# control.net
KiCad netlist of a schematic drawn in Altium Designer
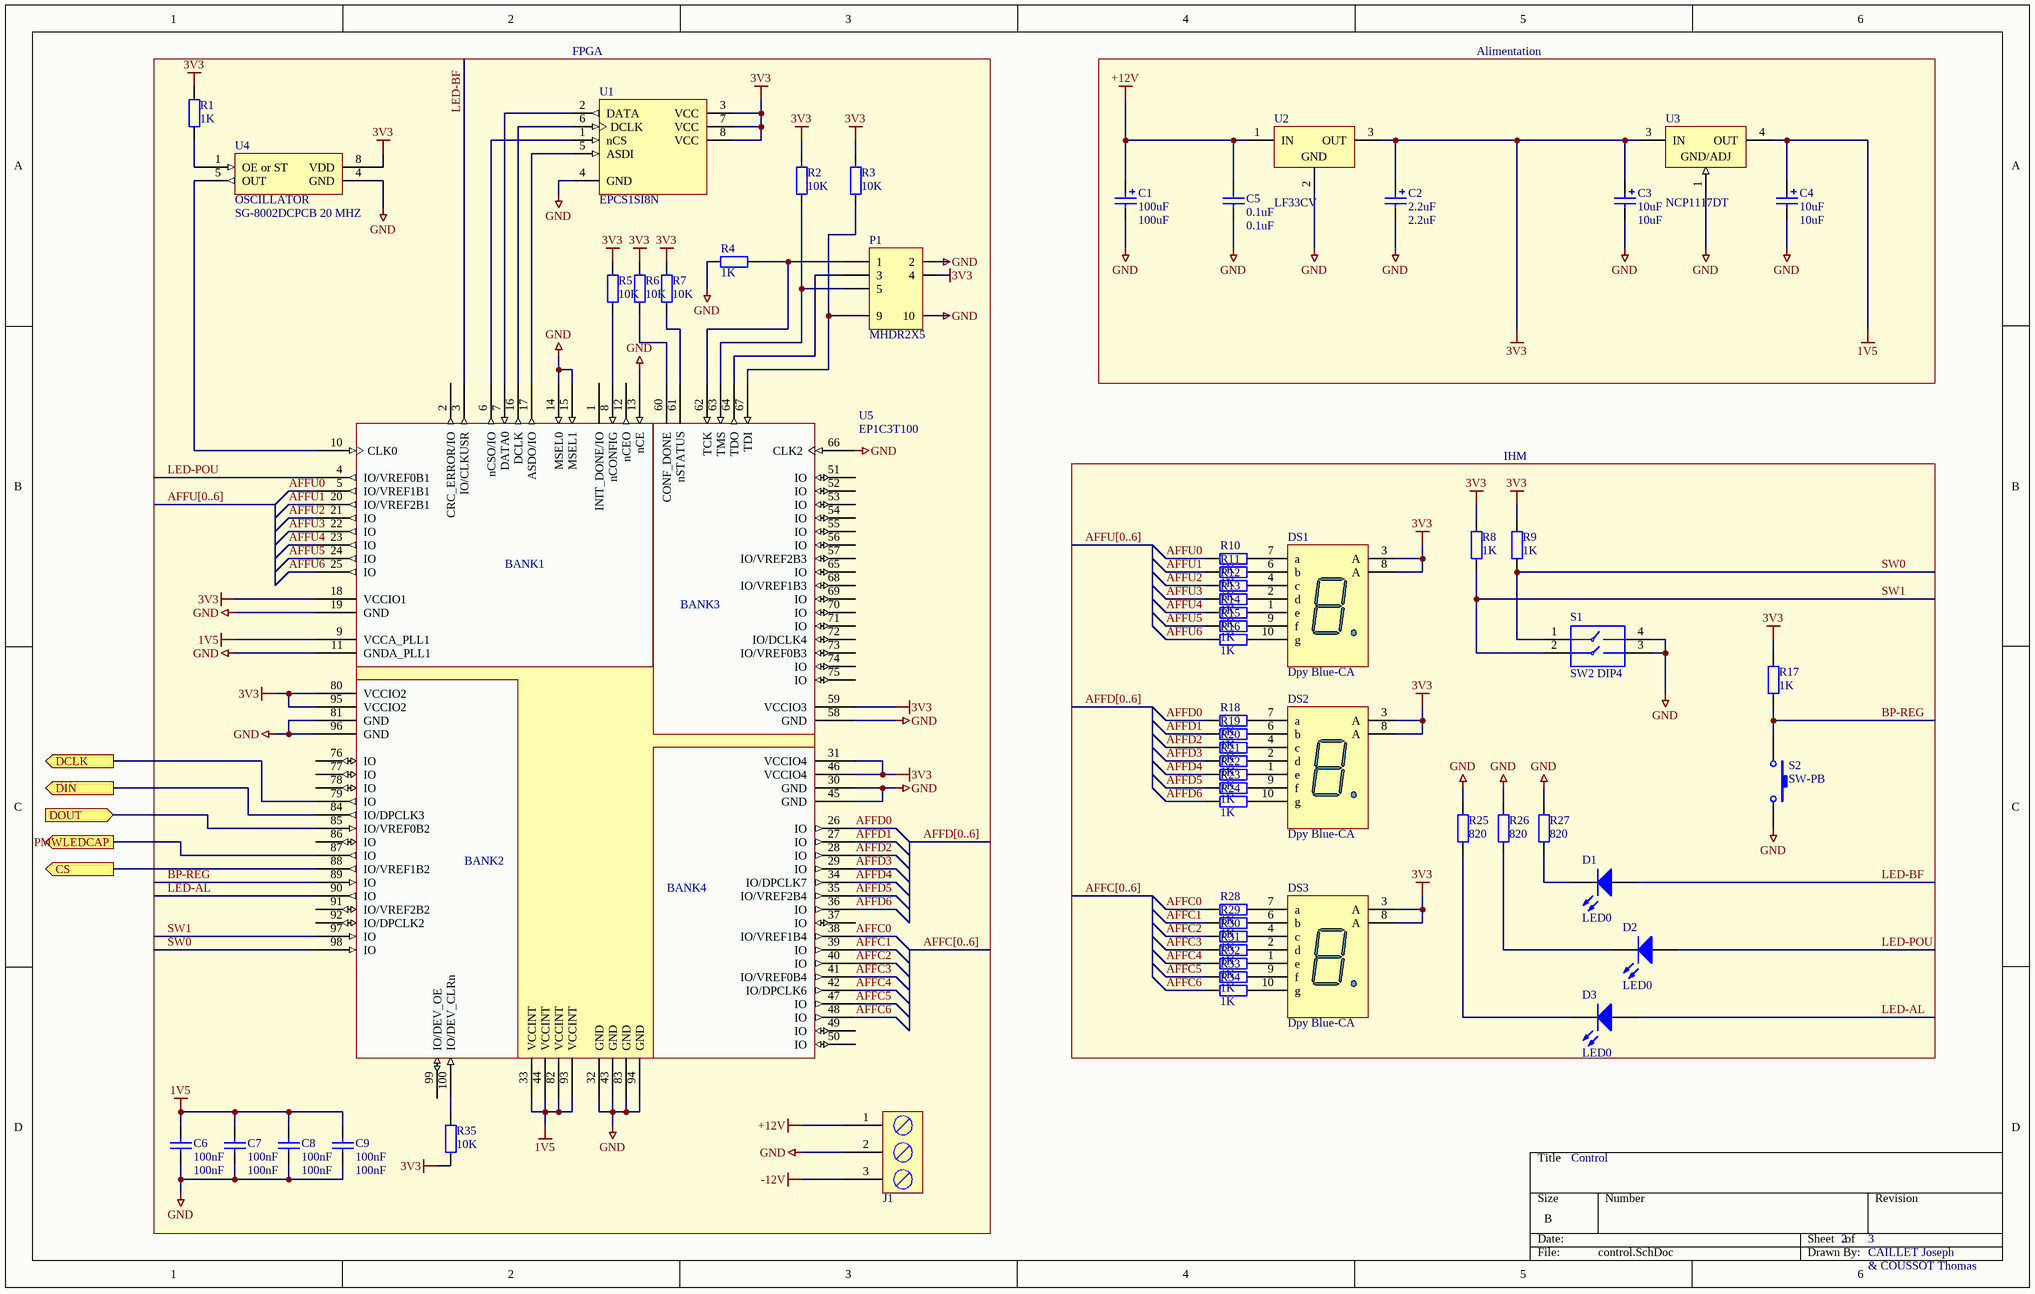
[diagram p0: control.SchDoc]

(export (version "E")
  (design (tool "Eeschema 10.0.6"))
  (components
    (comp (ref "C1")
      (value "100uF")
      (footprint "RB0.14/0.35")
      (description "Electrolytic Polarized Capacitor (Axial)")
      (fields (field (name "ALTIUM_VALUE") "100uF") (field (name "PUBLISHER") "Altium Limited"))
      (libsource (lib "Miscellaneous Devices") (part "Cap Pol2"))
    )
    (comp (ref "C2")
      (value "2.2uF")
      (footprint "RB0.1/0.2")
      (description "Electrolytic Polarized Capacitor (Axial)")
      (fields (field (name "ALTIUM_VALUE") "2.2uF") (field (name "PUBLISHER") "Altium Limited"))
      (libsource (lib "Miscellaneous Devices") (part "Cap Pol2"))
    )
    (comp (ref "C3")
      (value "10uF")
      (footprint "RB0.1/0.2")
      (description "Electrolytic Polarized Capacitor (Axial)")
      (fields (field (name "ALTIUM_VALUE") "10uF") (field (name "PUBLISHER") "Altium Limited"))
      (libsource (lib "Miscellaneous Devices") (part "Cap Pol2"))
    )
    (comp (ref "C4")
      (value "10uF")
      (footprint "RB0.1/0.2")
      (description "Electrolytic Polarized Capacitor (Axial)")
      (fields (field (name "ALTIUM_VALUE") "10uF") (field (name "PUBLISHER") "Altium Limited"))
      (libsource (lib "Miscellaneous Devices") (part "Cap Pol2"))
    )
    (comp (ref "C5")
      (value "0.1uF")
      (footprint "RAD-0.2")
      (description "Ceramic Multilayer Capacitor")
      (fields (field (name "ALTIUM_VALUE") "0.1uF") (field (name "PUBLISHER") "Altium Limited"))
      (libsource (lib "Miscellaneous Devices") (part "Cap"))
    )
    (comp (ref "C6")
      (value "100nF")
      (footprint "RAD-0.2")
      (description "Ceramic Multilayer Capacitor")
      (fields (field (name "ALTIUM_VALUE") "100nF") (field (name "PUBLISHER") "Altium Limited"))
      (libsource (lib "Miscellaneous Devices") (part "Cap"))
    )
    (comp (ref "C7")
      (value "100nF")
      (footprint "RAD-0.2")
      (description "Ceramic Multilayer Capacitor")
      (fields (field (name "ALTIUM_VALUE") "100nF") (field (name "PUBLISHER") "Altium Limited"))
      (libsource (lib "Miscellaneous Devices") (part "Cap"))
    )
    (comp (ref "C8")
      (value "100nF")
      (footprint "RAD-0.2")
      (description "Ceramic Multilayer Capacitor")
      (fields (field (name "ALTIUM_VALUE") "100nF") (field (name "PUBLISHER") "Altium Limited"))
      (libsource (lib "Miscellaneous Devices") (part "Cap"))
    )
    (comp (ref "C9")
      (value "100nF")
      (footprint "RAD-0.2")
      (description "Ceramic Multilayer Capacitor")
      (fields (field (name "ALTIUM_VALUE") "100nF") (field (name "PUBLISHER") "Altium Limited"))
      (libsource (lib "Miscellaneous Devices") (part "Cap"))
    )
    (comp (ref "D1")
      (value "LED0")
      (footprint "led-3mm")
      (description "Typical INFRARED GaAs LED")
      (fields (field (name "PUBLISHER") "Altium Limited"))
      (libsource (lib "Miscellaneous Devices") (part "LED0"))
    )
    (comp (ref "D2")
      (value "LED0")
      (footprint "led-3mm")
      (description "Typical INFRARED GaAs LED")
      (fields (field (name "PUBLISHER") "Altium Limited"))
      (libsource (lib "Miscellaneous Devices") (part "LED0"))
    )
    (comp (ref "D3")
      (value "LED0")
      (footprint "led-3mm")
      (description "Typical INFRARED GaAs LED")
      (fields (field (name "PUBLISHER") "Altium Limited"))
      (libsource (lib "Miscellaneous Devices") (part "LED0"))
    )
    (comp (ref "DS1")
      (value "Dpy Blue-CA")
      (footprint "AFF7SEG-14MM")
      (description "14.2 mm General Purpose Blue 7-Segment Display: CA, RH DP, Gray Surface")
      (fields (field (name "PUBLISHER") "Altium Limited"))
      (libsource (lib "Miscellaneous Devices") (part "Dpy Blue-CA"))
    )
    (comp (ref "DS2")
      (value "Dpy Blue-CA")
      (footprint "AFF7SEG-14MM")
      (description "14.2 mm General Purpose Blue 7-Segment Display: CA, RH DP, Gray Surface")
      (fields (field (name "PUBLISHER") "Altium Limited"))
      (libsource (lib "Miscellaneous Devices") (part "Dpy Blue-CA"))
    )
    (comp (ref "DS3")
      (value "Dpy Blue-CA")
      (footprint "AFF7SEG-14MM")
      (description "14.2 mm General Purpose Blue 7-Segment Display: CA, RH DP, Gray Surface")
      (fields (field (name "PUBLISHER") "Altium Limited"))
      (libsource (lib "Miscellaneous Devices") (part "Dpy Blue-CA"))
    )
    (comp (ref "J1")
      (value "BORNIER 3 VIS")
      (footprint "BORNIER-3")
      (description "Bornier 3 cts")
      (libsource (lib "schema_base_2016") (part "BORNIER-3"))
    )
    (comp (ref "P1")
      (value "MHDR2X5")
      (footprint "HE10-2X5M")
      (description "Header, 5-Pin, Dual row")
      (fields (field (name "PUBLISHER") "Altium Limited"))
      (libsource (lib "Miscellaneous Connectors") (part "MHDR2X5"))
    )
    (comp (ref "R1")
      (value "1K")
      (footprint "AXIAL-0.4")
      (description "Resistor")
      (fields (field (name "PUBLISHER") "Altium Limited"))
      (libsource (lib "") (part "Res2_1"))
    )
    (comp (ref "R2")
      (value "10K")
      (footprint "AXIAL-0.4")
      (description "Resistor")
      (fields (field (name "PUBLISHER") "Altium Limited"))
      (libsource (lib "") (part "Res2_1"))
    )
    (comp (ref "R3")
      (value "10K")
      (footprint "AXIAL-0.4")
      (description "Resistor")
      (fields (field (name "PUBLISHER") "Altium Limited"))
      (libsource (lib "") (part "Res2_1"))
    )
    (comp (ref "R4")
      (value "1K")
      (footprint "AXIAL-0.4")
      (description "Resistor")
      (fields (field (name "PUBLISHER") "Altium Limited"))
      (libsource (lib "") (part "Res2_3"))
    )
    (comp (ref "R5")
      (value "10K")
      (footprint "AXIAL-0.4")
      (description "Resistor")
      (fields (field (name "PUBLISHER") "Altium Limited"))
      (libsource (lib "") (part "Res2_1"))
    )
    (comp (ref "R6")
      (value "10K")
      (footprint "AXIAL-0.4")
      (description "Resistor")
      (fields (field (name "PUBLISHER") "Altium Limited"))
      (libsource (lib "") (part "Res2_1"))
    )
    (comp (ref "R7")
      (value "10K")
      (footprint "AXIAL-0.4")
      (description "Resistor")
      (fields (field (name "PUBLISHER") "Altium Limited"))
      (libsource (lib "") (part "Res2_1"))
    )
    (comp (ref "R8")
      (value "1K")
      (footprint "AXIAL-0.4")
      (description "Resistor")
      (fields (field (name "PUBLISHER") "Altium Limited"))
      (libsource (lib "Miscellaneous Devices") (part "Res2"))
    )
    (comp (ref "R9")
      (value "1K")
      (footprint "AXIAL-0.4")
      (description "Resistor")
      (fields (field (name "PUBLISHER") "Altium Limited"))
      (libsource (lib "Miscellaneous Devices") (part "Res2"))
    )
    (comp (ref "R10")
      (value "1K")
      (footprint "AXIAL-0.4")
      (description "Resistor")
      (fields (field (name "PUBLISHER") "Altium Limited"))
      (libsource (lib "") (part "Res2_2"))
    )
    (comp (ref "R11")
      (value "1K")
      (footprint "AXIAL-0.4")
      (description "Resistor")
      (fields (field (name "PUBLISHER") "Altium Limited"))
      (libsource (lib "") (part "Res2_2"))
    )
    (comp (ref "R12")
      (value "1K")
      (footprint "AXIAL-0.4")
      (description "Resistor")
      (fields (field (name "PUBLISHER") "Altium Limited"))
      (libsource (lib "") (part "Res2_2"))
    )
    (comp (ref "R13")
      (value "1K")
      (footprint "AXIAL-0.4")
      (description "Resistor")
      (fields (field (name "PUBLISHER") "Altium Limited"))
      (libsource (lib "") (part "Res2_2"))
    )
    (comp (ref "R14")
      (value "1K")
      (footprint "AXIAL-0.4")
      (description "Resistor")
      (fields (field (name "PUBLISHER") "Altium Limited"))
      (libsource (lib "") (part "Res2_2"))
    )
    (comp (ref "R15")
      (value "1K")
      (footprint "AXIAL-0.4")
      (description "Resistor")
      (fields (field (name "PUBLISHER") "Altium Limited"))
      (libsource (lib "") (part "Res2_2"))
    )
    (comp (ref "R16")
      (value "1K")
      (footprint "AXIAL-0.4")
      (description "Resistor")
      (fields (field (name "PUBLISHER") "Altium Limited"))
      (libsource (lib "") (part "Res2_2"))
    )
    (comp (ref "R17")
      (value "1K")
      (footprint "AXIAL-0.4")
      (description "Resistor")
      (fields (field (name "PUBLISHER") "Altium Limited"))
      (libsource (lib "Miscellaneous Devices") (part "Res2"))
    )
    (comp (ref "R18")
      (value "1K")
      (footprint "AXIAL-0.4")
      (description "Resistor")
      (fields (field (name "PUBLISHER") "Altium Limited"))
      (libsource (lib "") (part "Res2_2"))
    )
    (comp (ref "R19")
      (value "1K")
      (footprint "AXIAL-0.4")
      (description "Resistor")
      (fields (field (name "PUBLISHER") "Altium Limited"))
      (libsource (lib "") (part "Res2_2"))
    )
    (comp (ref "R20")
      (value "1K")
      (footprint "AXIAL-0.4")
      (description "Resistor")
      (fields (field (name "PUBLISHER") "Altium Limited"))
      (libsource (lib "") (part "Res2_2"))
    )
    (comp (ref "R21")
      (value "1K")
      (footprint "AXIAL-0.4")
      (description "Resistor")
      (fields (field (name "PUBLISHER") "Altium Limited"))
      (libsource (lib "") (part "Res2_2"))
    )
    (comp (ref "R22")
      (value "1K")
      (footprint "AXIAL-0.4")
      (description "Resistor")
      (fields (field (name "PUBLISHER") "Altium Limited"))
      (libsource (lib "") (part "Res2_2"))
    )
    (comp (ref "R23")
      (value "1K")
      (footprint "AXIAL-0.4")
      (description "Resistor")
      (fields (field (name "PUBLISHER") "Altium Limited"))
      (libsource (lib "") (part "Res2_2"))
    )
    (comp (ref "R24")
      (value "1K")
      (footprint "AXIAL-0.4")
      (description "Resistor")
      (fields (field (name "PUBLISHER") "Altium Limited"))
      (libsource (lib "") (part "Res2_2"))
    )
    (comp (ref "R25")
      (value "820")
      (footprint "AXIAL-0.4")
      (description "Resistor")
      (fields (field (name "PUBLISHER") "Altium Limited"))
      (libsource (lib "Miscellaneous Devices") (part "Res2"))
    )
    (comp (ref "R26")
      (value "820")
      (footprint "AXIAL-0.4")
      (description "Resistor")
      (fields (field (name "PUBLISHER") "Altium Limited"))
      (libsource (lib "Miscellaneous Devices") (part "Res2"))
    )
    (comp (ref "R27")
      (value "820")
      (footprint "AXIAL-0.4")
      (description "Resistor")
      (fields (field (name "PUBLISHER") "Altium Limited"))
      (libsource (lib "Miscellaneous Devices") (part "Res2"))
    )
    (comp (ref "R28")
      (value "1K")
      (footprint "AXIAL-0.4")
      (description "Resistor")
      (fields (field (name "PUBLISHER") "Altium Limited"))
      (libsource (lib "") (part "Res2_2"))
    )
    (comp (ref "R29")
      (value "1K")
      (footprint "AXIAL-0.4")
      (description "Resistor")
      (fields (field (name "PUBLISHER") "Altium Limited"))
      (libsource (lib "") (part "Res2_2"))
    )
    (comp (ref "R30")
      (value "1K")
      (footprint "AXIAL-0.4")
      (description "Resistor")
      (fields (field (name "PUBLISHER") "Altium Limited"))
      (libsource (lib "") (part "Res2_2"))
    )
    (comp (ref "R31")
      (value "1K")
      (footprint "AXIAL-0.4")
      (description "Resistor")
      (fields (field (name "PUBLISHER") "Altium Limited"))
      (libsource (lib "") (part "Res2_2"))
    )
    (comp (ref "R32")
      (value "1K")
      (footprint "AXIAL-0.4")
      (description "Resistor")
      (fields (field (name "PUBLISHER") "Altium Limited"))
      (libsource (lib "") (part "Res2_2"))
    )
    (comp (ref "R33")
      (value "1K")
      (footprint "AXIAL-0.4")
      (description "Resistor")
      (fields (field (name "PUBLISHER") "Altium Limited"))
      (libsource (lib "") (part "Res2_2"))
    )
    (comp (ref "R34")
      (value "1K")
      (footprint "AXIAL-0.4")
      (description "Resistor")
      (fields (field (name "PUBLISHER") "Altium Limited"))
      (libsource (lib "") (part "Res2_2"))
    )
    (comp (ref "R35")
      (value "10K")
      (footprint "AXIAL-0.4")
      (description "Resistor")
      (fields (field (name "PUBLISHER") "Altium Limited"))
      (libsource (lib "") (part "Res2_1"))
    )
    (comp (ref "S1")
      (value "SW2 DIP4")
      (footprint "DIP-4")
      (description "Dual Switch in DIP 4 pin")
      (fields (field (name "MANUFACTURER") "Generic Components") (field (name "PUBLISHER") "Altium Limited"))
      (libsource (lib "schema_base_2016") (part "SW2-DIP4"))
    )
    (comp (ref "S2")
      (value "SW-PB")
      (footprint "BP-MJTP12")
      (description "Switch")
      (fields (field (name "PUBLISHER") "Altium Limited"))
      (libsource (lib "Miscellaneous Devices") (part "SW-PB"))
    )
    (comp (ref "U1")
      (value "EPCS1SI8N")
      (footprint "DIP-8")
      (fields (field (name "PUBLISHER") "Altium Limited"))
      (libsource (lib "Altera EPCS Configuration Device") (part "EPCS1SI8N"))
    )
    (comp (ref "U2")
      (value "LF33CV")
      (footprint "REG-TO220")
      (description "500mA, Very Low Drop (0.45V) Voltage Regulator")
      (fields (field (name "PUBLISHER") "Altium Limited"))
      (libsource (lib "ST Power Mgt Voltage Regulator") (part "LF33CV"))
    )
    (comp (ref "U3")
      (value "NCP1117DT")
      (footprint "REG-DPAK")
      (description "Low drop out Positive Fix. or Adj. Voltage Regulator")
      (fields (field (name "MANUFACTURER") "ON Semiconductor"))
      (libsource (lib "schema_base_2016") (part "NCP1117DT"))
    )
    (comp (ref "U4")
      (value "SG-8002DCPCB 20 MHZ")
      (footprint "DIP-8")
      (description "OSCILLATOR SG-8002DCPCB 20 MHZ 5V")
      (fields (field (name "MANUFACTURER") "EPSON"))
      (libsource (lib "control") (part "SG-8002DCPCB 20 MHZ"))
    )
    (comp (ref "U5")
      (value "EP1C3T100")
      (footprint "SUPPORT-TQFP100")
      (description "FPGA CYCLONE 1 TQPF100")
      (fields (field (name "MANUFACTURER") "ALTERA"))
      (libsource (lib "schema_base_2016") (part "EP1C3T100"))
    )
  )
  (nets
    (net (code "1") (name "+12V") (class "Default")
      (node (ref "C1") (pin "1") (pinfunction "1_1") (pintype "passive"))
      (node (ref "C5") (pin "2") (pinfunction "2_2") (pintype "passive"))
      (node (ref "J1") (pin "1") (pinfunction "X_1") (pintype "passive"))
      (node (ref "U2") (pin "1") (pinfunction "IN_1") (pintype "power_in"))
    )
    (net (code "2") (name "-12V") (class "Default") (node (ref "J1") (pin "3") (pintype "passive")))
    (net (code "3") (name "/AFFC0") (class "Default")
      (node (ref "R28") (pin "1") (pinfunction "1_1") (pintype "passive"))
      (node (ref "U5") (pin "38") (pinfunction "IO/VREF1B4_38") (pintype "output"))
    )
    (net (code "4") (name "/AFFC1") (class "Default")
      (node (ref "R29") (pin "1") (pinfunction "1_1") (pintype "passive"))
      (node (ref "U5") (pin "39") (pinfunction "IO_39") (pintype "output"))
    )
    (net (code "5") (name "/AFFC2") (class "Default")
      (node (ref "R30") (pin "1") (pinfunction "1_1") (pintype "passive"))
      (node (ref "U5") (pin "40") (pinfunction "IO_40") (pintype "output"))
    )
    (net (code "6") (name "/AFFC3") (class "Default")
      (node (ref "R31") (pin "1") (pinfunction "1_1") (pintype "passive"))
      (node (ref "U5") (pin "41") (pinfunction "IO/VREF0B4_41") (pintype "output"))
    )
    (net (code "7") (name "/AFFC4") (class "Default")
      (node (ref "R32") (pin "1") (pinfunction "1_1") (pintype "passive"))
      (node (ref "U5") (pin "42") (pinfunction "IO/DPCLK6_42") (pintype "output"))
    )
    (net (code "8") (name "/AFFC5") (class "Default")
      (node (ref "R33") (pin "1") (pinfunction "1_1") (pintype "passive"))
      (node (ref "U5") (pin "47") (pinfunction "IO_47") (pintype "output"))
    )
    (net (code "9") (name "/AFFC6") (class "Default")
      (node (ref "R34") (pin "1") (pinfunction "1_1") (pintype "passive"))
      (node (ref "U5") (pin "48") (pinfunction "IO_48") (pintype "output"))
    )
    (net (code "11") (name "/AFFD0") (class "Default")
      (node (ref "R18") (pin "1") (pinfunction "1_1") (pintype "passive"))
      (node (ref "U5") (pin "26") (pinfunction "IO_26") (pintype "output"))
    )
    (net (code "12") (name "/AFFD1") (class "Default")
      (node (ref "R19") (pin "1") (pinfunction "1_1") (pintype "passive"))
      (node (ref "U5") (pin "27") (pinfunction "IO_27") (pintype "output"))
    )
    (net (code "13") (name "/AFFD2") (class "Default")
      (node (ref "R20") (pin "1") (pinfunction "1_1") (pintype "passive"))
      (node (ref "U5") (pin "28") (pinfunction "IO_28") (pintype "output"))
    )
    (net (code "14") (name "/AFFD3") (class "Default")
      (node (ref "R21") (pin "1") (pinfunction "1_1") (pintype "passive"))
      (node (ref "U5") (pin "29") (pinfunction "IO_29") (pintype "output"))
    )
    (net (code "15") (name "/AFFD4") (class "Default")
      (node (ref "R22") (pin "1") (pinfunction "1_1") (pintype "passive"))
      (node (ref "U5") (pin "34") (pinfunction "IO/DPCLK7_34") (pintype "output"))
    )
    (net (code "16") (name "/AFFD5") (class "Default")
      (node (ref "R23") (pin "1") (pinfunction "1_1") (pintype "passive"))
      (node (ref "U5") (pin "35") (pinfunction "IO/VREF2B4_35") (pintype "output"))
    )
    (net (code "17") (name "/AFFD6") (class "Default")
      (node (ref "R24") (pin "1") (pinfunction "1_1") (pintype "passive"))
      (node (ref "U5") (pin "36") (pinfunction "IO_36") (pintype "output"))
    )
    (net (code "19") (name "/AFFU0") (class "Default")
      (node (ref "R10") (pin "1") (pinfunction "1_1") (pintype "passive"))
      (node (ref "U5") (pin "5") (pinfunction "IO/VREF1B1_5") (pintype "output"))
    )
    (net (code "20") (name "/AFFU1") (class "Default")
      (node (ref "R11") (pin "1") (pinfunction "1_1") (pintype "passive"))
      (node (ref "U5") (pin "20") (pinfunction "IO/VREF2B1_20") (pintype "output"))
    )
    (net (code "21") (name "/AFFU2") (class "Default")
      (node (ref "R12") (pin "1") (pinfunction "1_1") (pintype "passive"))
      (node (ref "U5") (pin "21") (pinfunction "IO_21") (pintype "output"))
    )
    (net (code "22") (name "/AFFU3") (class "Default")
      (node (ref "R13") (pin "1") (pinfunction "1_1") (pintype "passive"))
      (node (ref "U5") (pin "22") (pinfunction "IO_22") (pintype "output"))
    )
    (net (code "23") (name "/AFFU4") (class "Default")
      (node (ref "R14") (pin "1") (pinfunction "1_1") (pintype "passive"))
      (node (ref "U5") (pin "23") (pinfunction "IO_23") (pintype "output"))
    )
    (net (code "24") (name "/AFFU5") (class "Default")
      (node (ref "R15") (pin "1") (pinfunction "1_1") (pintype "passive"))
      (node (ref "U5") (pin "24") (pinfunction "IO_24") (pintype "output"))
    )
    (net (code "25") (name "/AFFU6") (class "Default")
      (node (ref "R16") (pin "1") (pinfunction "1_1") (pintype "passive"))
      (node (ref "U5") (pin "25") (pinfunction "IO_25") (pintype "output"))
    )
    (net (code "27") (name "/BP-REG") (class "Default")
      (node (ref "R17") (pin "1") (pinfunction "1_1") (pintype "passive"))
      (node (ref "S2") (pin "1") (pinfunction "1_1") (pintype "passive"))
      (node (ref "U5") (pin "89") (pinfunction "IO_89") (pintype "input"))
    )
    (net (code "28") (name "/CS") (class "Default")
      (node (ref "U5") (pin "88") (pinfunction "IO/VREF1B2_88") (pintype "output"))
    )
    (net (code "29") (name "/DCLK") (class "Default")
      (node (ref "U5") (pin "79") (pinfunction "IO_79") (pintype "output"))
    )
    (net (code "30") (name "/DIN") (class "Default")
      (node (ref "U5") (pin "84") (pinfunction "IO/DPCLK3_84") (pintype "output"))
    )
    (net (code "31") (name "/DOUT") (class "Default")
      (node (ref "U5") (pin "85") (pinfunction "IO/VREF0B2_85") (pintype "input"))
    )
    (net (code "32") (name "/LED-AL") (class "Default")
      (node (ref "D3") (pin "1") (pinfunction "A_1") (pintype "passive"))
      (node (ref "U5") (pin "90") (pinfunction "IO_90") (pintype "output"))
    )
    (net (code "33") (name "/LED-BF") (class "Default")
      (node (ref "D1") (pin "1") (pinfunction "A_1") (pintype "passive"))
      (node (ref "U5") (pin "3") (pinfunction "IO/CLKUSR_3") (pintype "output"))
    )
    (net (code "34") (name "/LED-POU") (class "Default")
      (node (ref "D2") (pin "1") (pinfunction "A_1") (pintype "passive"))
      (node (ref "U5") (pin "4") (pinfunction "IO/VREF0B1_4") (pintype "output"))
    )
    (net (code "35") (name "/PMWLEDCAP") (class "Default")
      (node (ref "U5") (pin "87") (pinfunction "IO_87") (pintype "output"))
    )
    (net (code "36") (name "/SW0") (class "Default")
      (node (ref "R9") (pin "1") (pinfunction "1_1") (pintype "passive"))
      (node (ref "S1") (pin "1") (pinfunction "1_1") (pintype "passive"))
      (node (ref "U5") (pin "98") (pinfunction "IO_98") (pintype "input"))
    )
    (net (code "37") (name "/SW1") (class "Default")
      (node (ref "R8") (pin "1") (pinfunction "1_1") (pintype "passive"))
      (node (ref "S1") (pin "2") (pinfunction "2_2") (pintype "passive"))
      (node (ref "U5") (pin "97") (pinfunction "IO_97") (pintype "input"))
    )
    (net (code "38") (name "1V5") (class "Default")
      (node (ref "C4") (pin "1") (pinfunction "1_1") (pintype "passive"))
      (node (ref "C6") (pin "2") (pinfunction "2_2") (pintype "passive"))
      (node (ref "C7") (pin "2") (pinfunction "2_2") (pintype "passive"))
      (node (ref "C8") (pin "2") (pinfunction "2_2") (pintype "passive"))
      (node (ref "C9") (pin "2") (pinfunction "2_2") (pintype "passive"))
      (node (ref "U3") (pin "4") (pinfunction "OUT_4") (pintype "power_in"))
      (node (ref "U5") (pin "33") (pinfunction "VCCINT_33") (pintype "power_in"))
      (node (ref "U5") (pin "44") (pinfunction "VCCINT_44") (pintype "power_in"))
      (node (ref "U5") (pin "82") (pinfunction "VCCINT_82") (pintype "power_in"))
      (node (ref "U5") (pin "9") (pinfunction "VCCA_PLL1_9") (pintype "passive"))
      (node (ref "U5") (pin "93") (pinfunction "VCCINT_93") (pintype "power_in"))
    )
    (net (code "39") (name "3V3") (class "Default")
      (node (ref "C2") (pin "1") (pinfunction "1_1") (pintype "passive"))
      (node (ref "C3") (pin "1") (pinfunction "1_1") (pintype "passive"))
      (node (ref "DS1") (pin "3") (pinfunction "A_3") (pintype "passive"))
      (node (ref "DS1") (pin "8") (pinfunction "A_8") (pintype "passive"))
      (node (ref "DS2") (pin "3") (pinfunction "A_3") (pintype "passive"))
      (node (ref "DS2") (pin "8") (pinfunction "A_8") (pintype "passive"))
      (node (ref "DS3") (pin "3") (pinfunction "A_3") (pintype "passive"))
      (node (ref "DS3") (pin "8") (pinfunction "A_8") (pintype "passive"))
      (node (ref "P1") (pin "4") (pinfunction "4_4") (pintype "passive"))
      (node (ref "R1") (pin "1") (pinfunction "1_1") (pintype "passive"))
      (node (ref "R17") (pin "2") (pinfunction "2_2") (pintype "passive"))
      (node (ref "R2") (pin "1") (pinfunction "1_1") (pintype "passive"))
      (node (ref "R3") (pin "1") (pinfunction "1_1") (pintype "passive"))
      (node (ref "R35") (pin "2") (pinfunction "2_2") (pintype "passive"))
      (node (ref "R5") (pin "1") (pinfunction "1_1") (pintype "passive"))
      (node (ref "R6") (pin "1") (pinfunction "1_1") (pintype "passive"))
      (node (ref "R7") (pin "1") (pinfunction "1_1") (pintype "passive"))
      (node (ref "R8") (pin "2") (pinfunction "2_2") (pintype "passive"))
      (node (ref "R9") (pin "2") (pinfunction "2_2") (pintype "passive"))
      (node (ref "U1") (pin "3") (pinfunction "VCC_3") (pintype "power_in"))
      (node (ref "U1") (pin "7") (pinfunction "VCC_7") (pintype "power_in"))
      (node (ref "U1") (pin "8") (pinfunction "VCC_8") (pintype "power_in"))
      (node (ref "U2") (pin "3") (pinfunction "OUT_3") (pintype "power_in"))
      (node (ref "U3") (pin "3") (pinfunction "IN_3") (pintype "power_in"))
      (node (ref "U4") (pin "8") (pinfunction "VDD_8") (pintype "power_in"))
      (node (ref "U5") (pin "18") (pinfunction "VCCIO1_18") (pintype "power_in"))
      (node (ref "U5") (pin "31") (pinfunction "VCCIO4_31") (pintype "power_in"))
      (node (ref "U5") (pin "46") (pinfunction "VCCIO4_46") (pintype "power_in"))
      (node (ref "U5") (pin "59") (pinfunction "VCCIO3_59") (pintype "power_in"))
      (node (ref "U5") (pin "80") (pinfunction "VCCIO2_80") (pintype "power_in"))
      (node (ref "U5") (pin "95") (pinfunction "VCCIO2_95") (pintype "power_in"))
    )
    (net (code "40") (name "GND") (class "Default")
      (node (ref "C1") (pin "2") (pinfunction "2_2") (pintype "passive"))
      (node (ref "C2") (pin "2") (pinfunction "2_2") (pintype "passive"))
      (node (ref "C3") (pin "2") (pinfunction "2_2") (pintype "passive"))
      (node (ref "C4") (pin "2") (pinfunction "2_2") (pintype "passive"))
      (node (ref "C5") (pin "1") (pinfunction "1_1") (pintype "passive"))
      (node (ref "C6") (pin "1") (pinfunction "1_1") (pintype "passive"))
      (node (ref "C7") (pin "1") (pinfunction "1_1") (pintype "passive"))
      (node (ref "C8") (pin "1") (pinfunction "1_1") (pintype "passive"))
      (node (ref "C9") (pin "1") (pinfunction "1_1") (pintype "passive"))
      (node (ref "J1") (pin "2") (pintype "passive"))
      (node (ref "P1") (pin "10") (pinfunction "10_10") (pintype "passive"))
      (node (ref "P1") (pin "2") (pinfunction "2_2") (pintype "passive"))
      (node (ref "R25") (pin "2") (pinfunction "2_2") (pintype "passive"))
      (node (ref "R26") (pin "2") (pinfunction "2_2") (pintype "passive"))
      (node (ref "R27") (pin "2") (pinfunction "2_2") (pintype "passive"))
      (node (ref "R4") (pin "2") (pinfunction "2_2") (pintype "passive"))
      (node (ref "S1") (pin "3") (pinfunction "3_3") (pintype "passive"))
      (node (ref "S1") (pin "4") (pinfunction "4_4") (pintype "passive"))
      (node (ref "S2") (pin "2") (pinfunction "2_2") (pintype "passive"))
      (node (ref "U1") (pin "4") (pinfunction "GND_4") (pintype "power_in"))
      (node (ref "U2") (pin "2") (pinfunction "GND_2") (pintype "power_in"))
      (node (ref "U3") (pin "1") (pinfunction "GND/ADJ_1") (pintype "input"))
      (node (ref "U4") (pin "4") (pinfunction "GND_4") (pintype "power_in"))
      (node (ref "U5") (pin "11") (pinfunction "GNDA_PLL1_11") (pintype "passive"))
      (node (ref "U5") (pin "13") (pinfunction "nCE_13") (pintype "input"))
      (node (ref "U5") (pin "14") (pinfunction "MSEL0_14") (pintype "input"))
      (node (ref "U5") (pin "15") (pinfunction "MSEL1_15") (pintype "input"))
      (node (ref "U5") (pin "19") (pinfunction "GND_19") (pintype "power_in"))
      (node (ref "U5") (pin "30") (pinfunction "GND_30") (pintype "power_in"))
      (node (ref "U5") (pin "32") (pinfunction "GND_32") (pintype "power_in"))
      (node (ref "U5") (pin "43") (pinfunction "GND_43") (pintype "power_in"))
      (node (ref "U5") (pin "45") (pinfunction "GND_45") (pintype "power_in"))
      (node (ref "U5") (pin "58") (pinfunction "GND_58") (pintype "power_in"))
      (node (ref "U5") (pin "66") (pinfunction "CLK2_66") (pintype "input"))
      (node (ref "U5") (pin "81") (pinfunction "GND_81") (pintype "power_in"))
      (node (ref "U5") (pin "83") (pinfunction "GND_83") (pintype "power_in"))
      (node (ref "U5") (pin "94") (pinfunction "GND_94") (pintype "power_in"))
      (node (ref "U5") (pin "96") (pinfunction "GND_96") (pintype "power_in"))
    )
    (net (code "41") (name "Net-(D1-K)") (class "Default")
      (node (ref "D1") (pin "2") (pinfunction "K_2") (pintype "passive"))
      (node (ref "R27") (pin "1") (pinfunction "1_1") (pintype "passive"))
    )
    (net (code "42") (name "Net-(D2-K)") (class "Default")
      (node (ref "D2") (pin "2") (pinfunction "K_2") (pintype "passive"))
      (node (ref "R26") (pin "1") (pinfunction "1_1") (pintype "passive"))
    )
    (net (code "43") (name "Net-(D3-K)") (class "Default")
      (node (ref "D3") (pin "2") (pinfunction "K_2") (pintype "passive"))
      (node (ref "R25") (pin "1") (pinfunction "1_1") (pintype "passive"))
    )
    (net (code "44") (name "Net-(DS1-a)") (class "Default")
      (node (ref "DS1") (pin "7") (pinfunction "a_7") (pintype "passive"))
      (node (ref "R10") (pin "2") (pinfunction "2_2") (pintype "passive"))
    )
    (net (code "45") (name "Net-(DS1-b)") (class "Default")
      (node (ref "DS1") (pin "6") (pinfunction "b_6") (pintype "passive"))
      (node (ref "R11") (pin "2") (pinfunction "2_2") (pintype "passive"))
    )
    (net (code "46") (name "Net-(DS1-c)") (class "Default")
      (node (ref "DS1") (pin "4") (pinfunction "c_4") (pintype "passive"))
      (node (ref "R12") (pin "2") (pinfunction "2_2") (pintype "passive"))
    )
    (net (code "47") (name "Net-(DS1-d)") (class "Default")
      (node (ref "DS1") (pin "2") (pinfunction "d_2") (pintype "passive"))
      (node (ref "R13") (pin "2") (pinfunction "2_2") (pintype "passive"))
    )
    (net (code "48") (name "Net-(DS1-e)") (class "Default")
      (node (ref "DS1") (pin "1") (pinfunction "e_1") (pintype "passive"))
      (node (ref "R14") (pin "2") (pinfunction "2_2") (pintype "passive"))
    )
    (net (code "49") (name "Net-(DS1-f)") (class "Default")
      (node (ref "DS1") (pin "9") (pinfunction "f_9") (pintype "passive"))
      (node (ref "R15") (pin "2") (pinfunction "2_2") (pintype "passive"))
    )
    (net (code "50") (name "Net-(DS1-g)") (class "Default")
      (node (ref "DS1") (pin "10") (pinfunction "g_10") (pintype "passive"))
      (node (ref "R16") (pin "2") (pinfunction "2_2") (pintype "passive"))
    )
    (net (code "51") (name "Net-(DS2-a)") (class "Default")
      (node (ref "DS2") (pin "7") (pinfunction "a_7") (pintype "passive"))
      (node (ref "R18") (pin "2") (pinfunction "2_2") (pintype "passive"))
    )
    (net (code "52") (name "Net-(DS2-b)") (class "Default")
      (node (ref "DS2") (pin "6") (pinfunction "b_6") (pintype "passive"))
      (node (ref "R19") (pin "2") (pinfunction "2_2") (pintype "passive"))
    )
    (net (code "53") (name "Net-(DS2-c)") (class "Default")
      (node (ref "DS2") (pin "4") (pinfunction "c_4") (pintype "passive"))
      (node (ref "R20") (pin "2") (pinfunction "2_2") (pintype "passive"))
    )
    (net (code "54") (name "Net-(DS2-d)") (class "Default")
      (node (ref "DS2") (pin "2") (pinfunction "d_2") (pintype "passive"))
      (node (ref "R21") (pin "2") (pinfunction "2_2") (pintype "passive"))
    )
    (net (code "55") (name "Net-(DS2-e)") (class "Default")
      (node (ref "DS2") (pin "1") (pinfunction "e_1") (pintype "passive"))
      (node (ref "R22") (pin "2") (pinfunction "2_2") (pintype "passive"))
    )
    (net (code "56") (name "Net-(DS2-f)") (class "Default")
      (node (ref "DS2") (pin "9") (pinfunction "f_9") (pintype "passive"))
      (node (ref "R23") (pin "2") (pinfunction "2_2") (pintype "passive"))
    )
    (net (code "57") (name "Net-(DS2-g)") (class "Default")
      (node (ref "DS2") (pin "10") (pinfunction "g_10") (pintype "passive"))
      (node (ref "R24") (pin "2") (pinfunction "2_2") (pintype "passive"))
    )
    (net (code "58") (name "Net-(DS3-a)") (class "Default")
      (node (ref "DS3") (pin "7") (pinfunction "a_7") (pintype "passive"))
      (node (ref "R28") (pin "2") (pinfunction "2_2") (pintype "passive"))
    )
    (net (code "59") (name "Net-(DS3-b)") (class "Default")
      (node (ref "DS3") (pin "6") (pinfunction "b_6") (pintype "passive"))
      (node (ref "R29") (pin "2") (pinfunction "2_2") (pintype "passive"))
    )
    (net (code "60") (name "Net-(DS3-c)") (class "Default")
      (node (ref "DS3") (pin "4") (pinfunction "c_4") (pintype "passive"))
      (node (ref "R30") (pin "2") (pinfunction "2_2") (pintype "passive"))
    )
    (net (code "61") (name "Net-(DS3-d)") (class "Default")
      (node (ref "DS3") (pin "2") (pinfunction "d_2") (pintype "passive"))
      (node (ref "R31") (pin "2") (pinfunction "2_2") (pintype "passive"))
    )
    (net (code "62") (name "Net-(DS3-e)") (class "Default")
      (node (ref "DS3") (pin "1") (pinfunction "e_1") (pintype "passive"))
      (node (ref "R32") (pin "2") (pinfunction "2_2") (pintype "passive"))
    )
    (net (code "63") (name "Net-(DS3-f)") (class "Default")
      (node (ref "DS3") (pin "9") (pinfunction "f_9") (pintype "passive"))
      (node (ref "R33") (pin "2") (pinfunction "2_2") (pintype "passive"))
    )
    (net (code "64") (name "Net-(DS3-g)") (class "Default")
      (node (ref "DS3") (pin "10") (pinfunction "g_10") (pintype "passive"))
      (node (ref "R34") (pin "2") (pinfunction "2_2") (pintype "passive"))
    )
    (net (code "65") (name "Net-(U1-ASDI)") (class "Default")
      (node (ref "U1") (pin "5") (pinfunction "ASDI_5") (pintype "input"))
      (node (ref "U5") (pin "17") (pinfunction "ASDO/IO_17") (pintype "output"))
    )
    (net (code "66") (name "Net-(U1-DATA)") (class "Default")
      (node (ref "U1") (pin "2") (pinfunction "DATA_2") (pintype "output"))
      (node (ref "U5") (pin "7") (pinfunction "DATA0_7") (pintype "input"))
    )
    (net (code "67") (name "Net-(U1-DCLK)") (class "Default")
      (node (ref "U1") (pin "6") (pinfunction "DCLK_6") (pintype "input"))
      (node (ref "U5") (pin "16") (pinfunction "DCLK_16") (pintype "output"))
    )
    (net (code "68") (name "Net-(U1-nCS)") (class "Default")
      (node (ref "U1") (pin "1") (pinfunction "nCS_1") (pintype "input"))
      (node (ref "U5") (pin "6") (pinfunction "nCSO/IO_6") (pintype "output"))
    )
    (net (code "69") (name "Net-(U4-OE_or_ST)") (class "Default")
      (node (ref "R1") (pin "2") (pinfunction "2_2") (pintype "passive"))
      (node (ref "U4") (pin "1") (pinfunction "OE_or_ST_1") (pintype "input"))
    )
    (net (code "70") (name "Net-(U4-OUT)") (class "Default")
      (node (ref "U4") (pin "5") (pinfunction "OUT_5") (pintype "output"))
      (node (ref "U5") (pin "10") (pinfunction "CLK0_10") (pintype "input"))
    )
    (net (code "71") (name "Net-(U5-CONF_DONE)") (class "Default")
      (node (ref "R6") (pin "2") (pinfunction "2_2") (pintype "passive"))
      (node (ref "U5") (pin "60") (pinfunction "CONF_DONE_60") (pintype "open_collector"))
    )
    (net (code "72") (name "Net-(U5-IO{slash}DEV_CLRn)") (class "Default")
      (node (ref "R35") (pin "1") (pinfunction "1_1") (pintype "passive"))
      (node (ref "U5") (pin "100") (pinfunction "IO/DEV_CLRn_100") (pintype "input"))
    )
    (net (code "73") (name "Net-(U5-TCK)") (class "Default")
      (node (ref "P1") (pin "1") (pinfunction "1_1") (pintype "passive"))
      (node (ref "R4") (pin "1") (pinfunction "1_1") (pintype "passive"))
      (node (ref "U5") (pin "62") (pinfunction "TCK_62") (pintype "input"))
    )
    (net (code "74") (name "Net-(U5-TDI)") (class "Default")
      (node (ref "P1") (pin "9") (pinfunction "9_9") (pintype "passive"))
      (node (ref "R3") (pin "2") (pinfunction "2_2") (pintype "passive"))
      (node (ref "U5") (pin "67") (pinfunction "TDI_67") (pintype "input"))
    )
    (net (code "75") (name "Net-(U5-TDO)") (class "Default")
      (node (ref "P1") (pin "3") (pinfunction "3_3") (pintype "passive"))
      (node (ref "U5") (pin "64") (pinfunction "TDO_64") (pintype "output"))
    )
    (net (code "76") (name "Net-(U5-TMS)") (class "Default")
      (node (ref "P1") (pin "5") (pinfunction "5_5") (pintype "passive"))
      (node (ref "R2") (pin "2") (pinfunction "2_2") (pintype "passive"))
      (node (ref "U5") (pin "63") (pinfunction "TMS_63") (pintype "input"))
    )
    (net (code "77") (name "Net-(U5-nCONFIG)") (class "Default")
      (node (ref "R5") (pin "2") (pinfunction "2_2") (pintype "passive"))
      (node (ref "U5") (pin "8") (pinfunction "nCONFIG_8") (pintype "input"))
    )
    (net (code "78") (name "Net-(U5-nSTATUS)") (class "Default")
      (node (ref "R7") (pin "2") (pinfunction "2_2") (pintype "passive"))
      (node (ref "U5") (pin "61") (pinfunction "nSTATUS_61") (pintype "open_collector"))
    )
    (net (code "79") (name "unconnected-(DS1-DP-Pad5)") (class "Default")
      (node (ref "DS1") (pin "5") (pinfunction "DP_5") (pintype "passive"))
    )
    (net (code "80") (name "unconnected-(DS2-DP-Pad5)") (class "Default")
      (node (ref "DS2") (pin "5") (pinfunction "DP_5") (pintype "passive"))
    )
    (net (code "81") (name "unconnected-(DS3-DP-Pad5)") (class "Default")
      (node (ref "DS3") (pin "5") (pinfunction "DP_5") (pintype "passive"))
    )
    (net (code "82") (name "unconnected-(P1-Pad6)") (class "Default")
      (node (ref "P1") (pin "6") (pinfunction "6_6") (pintype "passive"))
    )
    (net (code "83") (name "unconnected-(P1-Pad7)") (class "Default")
      (node (ref "P1") (pin "7") (pinfunction "7_7") (pintype "passive"))
    )
    (net (code "84") (name "unconnected-(P1-Pad8)") (class "Default")
      (node (ref "P1") (pin "8") (pinfunction "8_8") (pintype "passive"))
    )
    (net (code "85") (name "unconnected-(U5-CRC_ERROR{slash}IO-Pad2)") (class "Default")
      (node (ref "U5") (pin "2") (pinfunction "CRC_ERROR/IO_2") (pintype "output"))
    )
    (net (code "86") (name "unconnected-(U5-INIT_DONE{slash}IO-Pad1)") (class "Default")
      (node (ref "U5") (pin "1") (pinfunction "INIT_DONE/IO_1") (pintype "open_collector"))
    )
    (net (code "87") (name "unconnected-(U5-IO-Pad37)") (class "Default")
      (node (ref "U5") (pin "37") (pinfunction "IO_37") (pintype "bidirectional"))
    )
    (net (code "88") (name "unconnected-(U5-IO-Pad49)") (class "Default")
      (node (ref "U5") (pin "49") (pinfunction "IO_49") (pintype "bidirectional"))
    )
    (net (code "89") (name "unconnected-(U5-IO-Pad50)") (class "Default")
      (node (ref "U5") (pin "50") (pinfunction "IO_50") (pintype "bidirectional"))
    )
    (net (code "90") (name "unconnected-(U5-IO-Pad51)") (class "Default")
      (node (ref "U5") (pin "51") (pinfunction "IO_51") (pintype "bidirectional"))
    )
    (net (code "91") (name "unconnected-(U5-IO-Pad52)") (class "Default")
      (node (ref "U5") (pin "52") (pinfunction "IO_52") (pintype "bidirectional"))
    )
    (net (code "92") (name "unconnected-(U5-IO-Pad53)") (class "Default")
      (node (ref "U5") (pin "53") (pinfunction "IO_53") (pintype "bidirectional"))
    )
    (net (code "93") (name "unconnected-(U5-IO-Pad54)") (class "Default")
      (node (ref "U5") (pin "54") (pinfunction "IO_54") (pintype "bidirectional"))
    )
    (net (code "94") (name "unconnected-(U5-IO-Pad55)") (class "Default")
      (node (ref "U5") (pin "55") (pinfunction "IO_55") (pintype "bidirectional"))
    )
    (net (code "95") (name "unconnected-(U5-IO-Pad56)") (class "Default")
      (node (ref "U5") (pin "56") (pinfunction "IO_56") (pintype "bidirectional"))
    )
    (net (code "96") (name "unconnected-(U5-IO-Pad65)") (class "Default")
      (node (ref "U5") (pin "65") (pinfunction "IO_65") (pintype "bidirectional"))
    )
    (net (code "97") (name "unconnected-(U5-IO-Pad69)") (class "Default")
      (node (ref "U5") (pin "69") (pinfunction "IO_69") (pintype "bidirectional"))
    )
    (net (code "98") (name "unconnected-(U5-IO-Pad70)") (class "Default")
      (node (ref "U5") (pin "70") (pinfunction "IO_70") (pintype "bidirectional"))
    )
    (net (code "99") (name "unconnected-(U5-IO-Pad71)") (class "Default")
      (node (ref "U5") (pin "71") (pinfunction "IO_71") (pintype "bidirectional"))
    )
    (net (code "100") (name "unconnected-(U5-IO-Pad74)") (class "Default")
      (node (ref "U5") (pin "74") (pinfunction "IO_74") (pintype "bidirectional"))
    )
    (net (code "101") (name "unconnected-(U5-IO-Pad75)") (class "Default")
      (node (ref "U5") (pin "75") (pinfunction "IO_75") (pintype "bidirectional"))
    )
    (net (code "102") (name "unconnected-(U5-IO-Pad76)") (class "Default")
      (node (ref "U5") (pin "76") (pinfunction "IO_76") (pintype "bidirectional"))
    )
    (net (code "103") (name "unconnected-(U5-IO-Pad77)") (class "Default")
      (node (ref "U5") (pin "77") (pinfunction "IO_77") (pintype "bidirectional"))
    )
    (net (code "104") (name "unconnected-(U5-IO-Pad78)") (class "Default")
      (node (ref "U5") (pin "78") (pinfunction "IO_78") (pintype "bidirectional"))
    )
    (net (code "105") (name "unconnected-(U5-IO-Pad86)") (class "Default")
      (node (ref "U5") (pin "86") (pinfunction "IO_86") (pintype "bidirectional"))
    )
    (net (code "106") (name "unconnected-(U5-IO{slash}DCLK4-Pad72)") (class "Default")
      (node (ref "U5") (pin "72") (pinfunction "IO/DCLK4_72") (pintype "bidirectional"))
    )
    (net (code "107") (name "unconnected-(U5-IO{slash}DEV_OE-Pad99)") (class "Default")
      (node (ref "U5") (pin "99") (pinfunction "IO/DEV_OE_99") (pintype "bidirectional"))
    )
    (net (code "108") (name "unconnected-(U5-IO{slash}DPCLK2-Pad92)") (class "Default")
      (node (ref "U5") (pin "92") (pinfunction "IO/DPCLK2_92") (pintype "bidirectional"))
    )
    (net (code "109") (name "unconnected-(U5-IO{slash}VREF0B3-Pad73)") (class "Default")
      (node (ref "U5") (pin "73") (pinfunction "IO/VREF0B3_73") (pintype "bidirectional"))
    )
    (net (code "110") (name "unconnected-(U5-IO{slash}VREF1B3-Pad68)") (class "Default")
      (node (ref "U5") (pin "68") (pinfunction "IO/VREF1B3_68") (pintype "bidirectional"))
    )
    (net (code "111") (name "unconnected-(U5-IO{slash}VREF2B2-Pad91)") (class "Default")
      (node (ref "U5") (pin "91") (pinfunction "IO/VREF2B2_91") (pintype "bidirectional"))
    )
    (net (code "112") (name "unconnected-(U5-IO{slash}VREF2B3-Pad57)") (class "Default")
      (node (ref "U5") (pin "57") (pinfunction "IO/VREF2B3_57") (pintype "bidirectional"))
    )
    (net (code "113") (name "unconnected-(U5-nCEO-Pad12)") (class "Default")
      (node (ref "U5") (pin "12") (pinfunction "nCEO_12") (pintype "output"))
    )
  )
)
